# 7seg247b.net
KiCad netlist of a schematic drawn in EAGLE
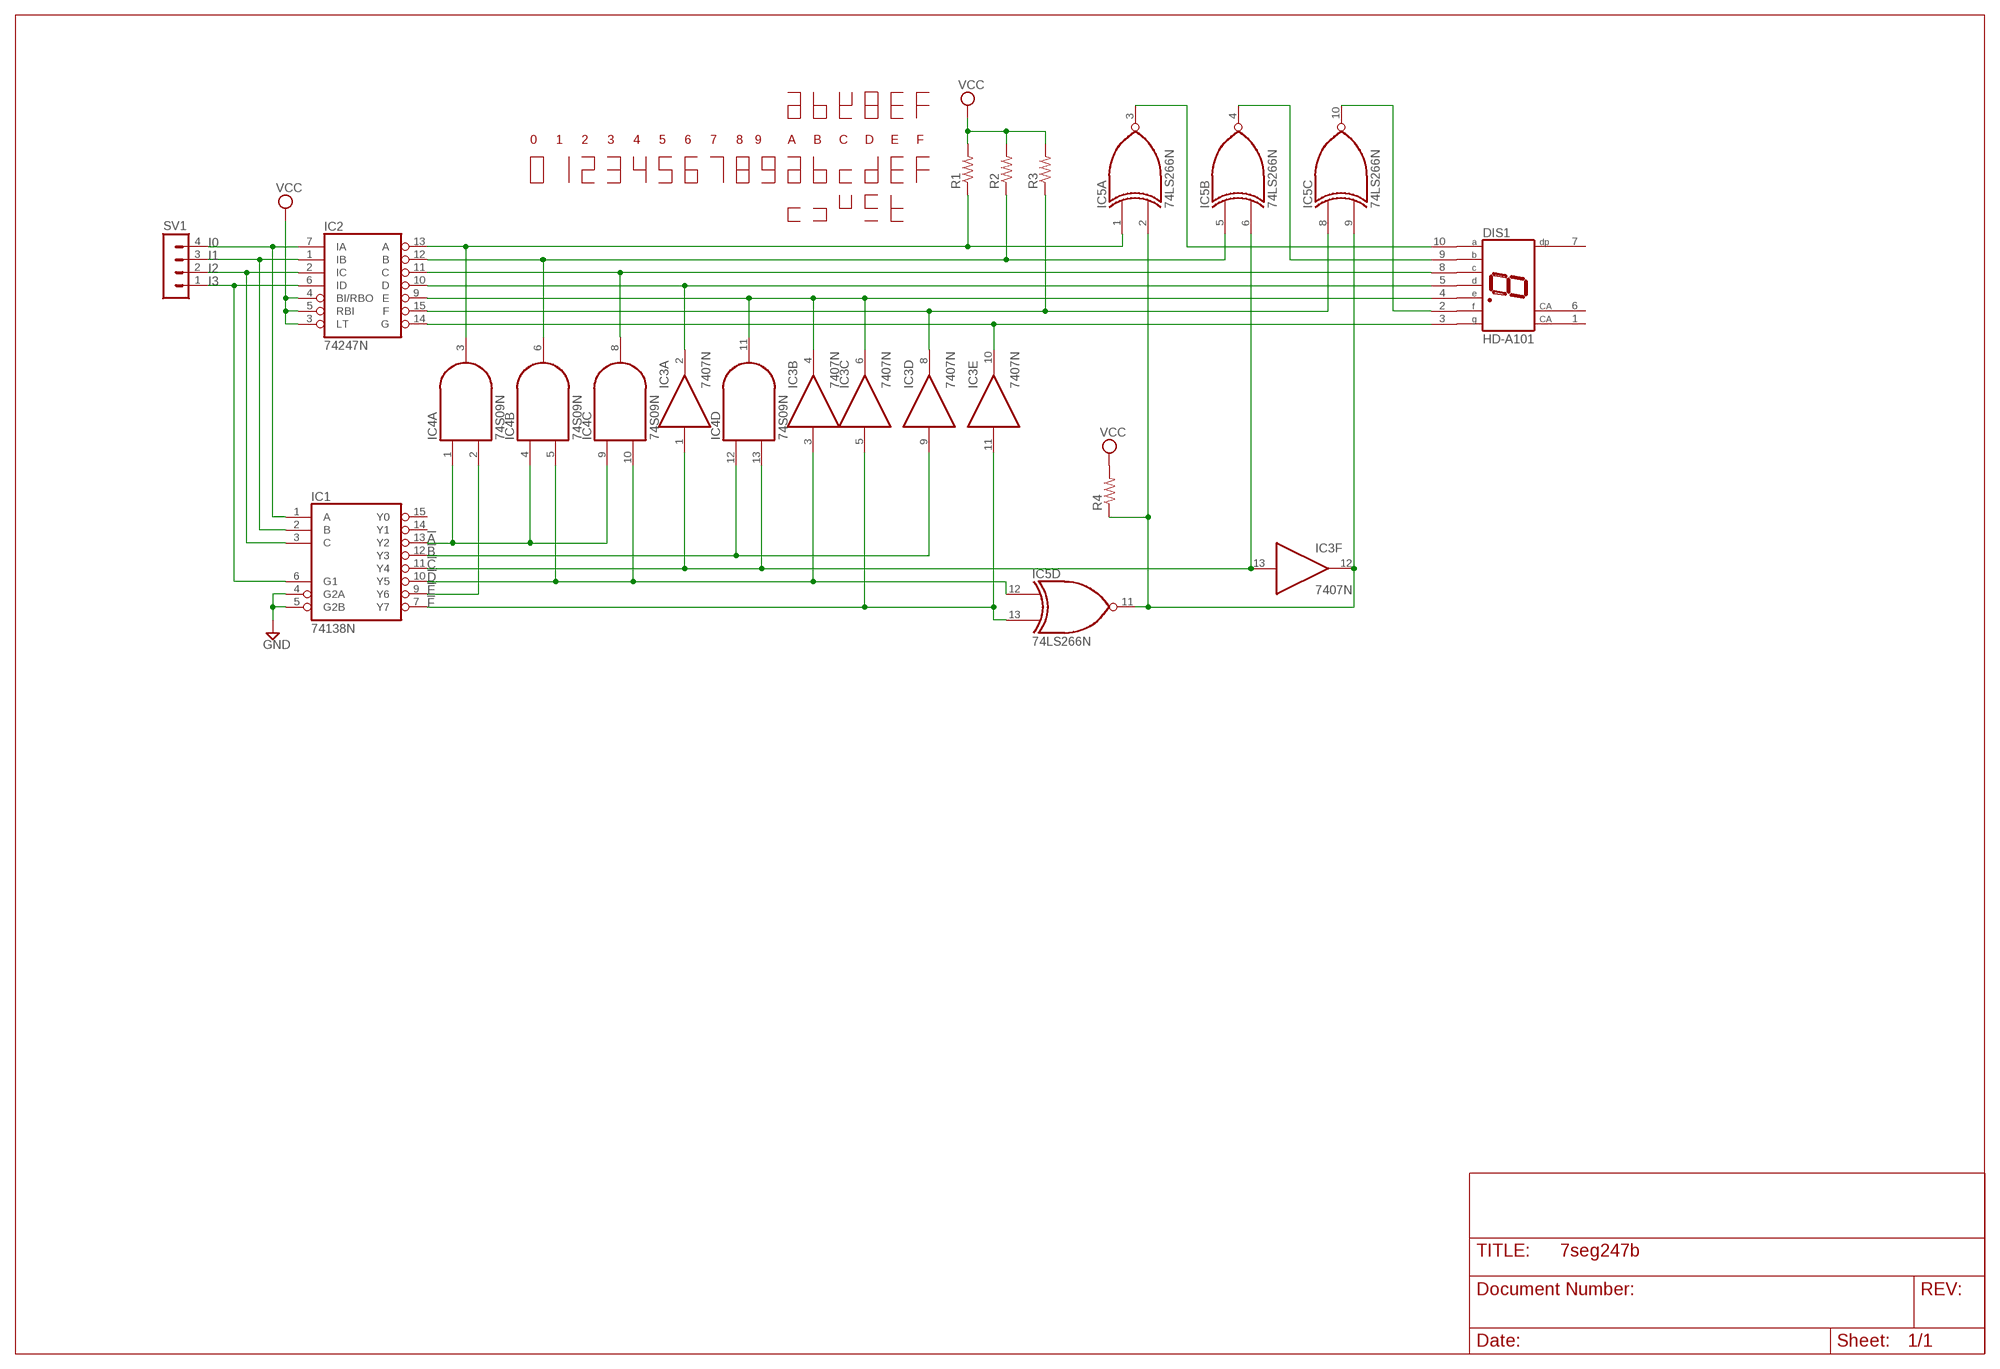
[diagram p0: schematic, sheet 1]

(export (version "E")
  (design (tool "Eeschema 10.0.6"))
  (components
    (comp (ref "DIS1")
      (value "HD-A101")
      (footprint "eagle-import:HDSP-A")
      (libsource (lib "eagle-import") (part "HD-A101"))
    )
    (comp (ref "IC1")
      (value "74138N")
      (footprint "eagle-import:DIL16")
      (libsource (lib "eagle-import") (part "74138NS"))
    )
    (comp (ref "IC2")
      (value "74247N")
      (footprint "eagle-import:DIL16")
      (libsource (lib "eagle-import") (part "7446N"))
    )
    (comp (ref "IC3")
      (value "7407N")
      (footprint "eagle-import:DIL14")
      (libsource (lib "eagle-import") (part "7407N"))
    )
    (comp (ref "IC4")
      (value "74S09N")
      (footprint "eagle-import:DIL14")
      (libsource (lib "eagle-import") (part "7409NS"))
    )
    (comp (ref "IC5")
      (value "74LS266N")
      (footprint "eagle-import:DIL14")
      (libsource (lib "eagle-import") (part "74266NLS"))
    )
    (comp (ref "R1")
      (value "R-US_0207/10")
      (footprint "eagle-import:0207_10")
      (libsource (lib "eagle-import") (part "R-US_0207/10"))
    )
    (comp (ref "R2")
      (value "R-US_0207/10")
      (footprint "eagle-import:0207_10")
      (libsource (lib "eagle-import") (part "R-US_0207/10"))
    )
    (comp (ref "R3")
      (value "R-US_0207/10")
      (footprint "eagle-import:0207_10")
      (libsource (lib "eagle-import") (part "R-US_0207/10"))
    )
    (comp (ref "R4")
      (value "R-US_0207/10")
      (footprint "eagle-import:0207_10")
      (libsource (lib "eagle-import") (part "R-US_0207/10"))
    )
    (comp (ref "SV1")
      (value "MA04-1")
      (footprint "eagle-import:MA04-1")
      (libsource (lib "eagle-import") (part "MA04-1"))
    )
  )
  (nets
    (net (code "1") (name "/I0") (class "Default")
      (node (ref "IC1") (pin "1") (pinfunction "A_1") (pintype "input"))
      (node (ref "IC2") (pin "7") (pinfunction "IA_7") (pintype "input"))
      (node (ref "SV1") (pin "4") (pinfunction "4_4") (pintype "passive"))
    )
    (net (code "2") (name "/I1") (class "Default")
      (node (ref "IC1") (pin "2") (pinfunction "B_2") (pintype "input"))
      (node (ref "IC2") (pin "1") (pinfunction "IB_1") (pintype "input"))
      (node (ref "SV1") (pin "3") (pinfunction "3_3") (pintype "passive"))
    )
    (net (code "3") (name "/I2") (class "Default")
      (node (ref "IC1") (pin "3") (pinfunction "C_3") (pintype "input"))
      (node (ref "IC2") (pin "2") (pinfunction "IC_2") (pintype "input"))
      (node (ref "SV1") (pin "2") (pinfunction "2_2") (pintype "passive"))
    )
    (net (code "4") (name "/I3") (class "Default")
      (node (ref "IC1") (pin "6") (pinfunction "G1_6") (pintype "input"))
      (node (ref "IC2") (pin "6") (pinfunction "ID_6") (pintype "input"))
      (node (ref "SV1") (pin "1") (pinfunction "1_1") (pintype "passive"))
    )
    (net (code "5") (name "/~{A}") (class "Default")
      (node (ref "IC1") (pin "13") (pinfunction "Y2_13") (pintype "output"))
      (node (ref "IC4") (pin "1") (pinfunction "I0_1") (pintype "input"))
      (node (ref "IC4") (pin "4") (pinfunction "I0_4") (pintype "input"))
      (node (ref "IC4") (pin "9") (pinfunction "I0_9") (pintype "input"))
    )
    (net (code "6") (name "/~{B}") (class "Default")
      (node (ref "IC1") (pin "12") (pinfunction "Y3_12") (pintype "output"))
      (node (ref "IC3") (pin "9") (pinfunction "I_9") (pintype "input"))
      (node (ref "IC4") (pin "12") (pinfunction "I0_12") (pintype "input"))
    )
    (net (code "7") (name "/~{C}") (class "Default")
      (node (ref "IC1") (pin "11") (pinfunction "Y4_11") (pintype "output"))
      (node (ref "IC3") (pin "1") (pinfunction "I_1") (pintype "input"))
      (node (ref "IC3") (pin "13") (pinfunction "I_13") (pintype "input"))
      (node (ref "IC4") (pin "13") (pinfunction "I1_13") (pintype "input"))
      (node (ref "IC5") (pin "6") (pinfunction "I1_6") (pintype "input"))
    )
    (net (code "8") (name "/~{D}") (class "Default")
      (node (ref "IC1") (pin "10") (pinfunction "Y5_10") (pintype "output"))
      (node (ref "IC3") (pin "3") (pinfunction "I_3") (pintype "input"))
      (node (ref "IC4") (pin "10") (pinfunction "I1_10") (pintype "input"))
      (node (ref "IC4") (pin "5") (pinfunction "I1_5") (pintype "input"))
      (node (ref "IC5") (pin "12") (pinfunction "I0_12") (pintype "input"))
    )
    (net (code "9") (name "/~{E}") (class "Default")
      (node (ref "IC1") (pin "9") (pinfunction "Y6_9") (pintype "output"))
      (node (ref "IC4") (pin "2") (pinfunction "I1_2") (pintype "input"))
    )
    (net (code "10") (name "/~{F}") (class "Default")
      (node (ref "IC1") (pin "7") (pinfunction "Y7_7") (pintype "output"))
      (node (ref "IC3") (pin "11") (pinfunction "I_11") (pintype "input"))
      (node (ref "IC3") (pin "5") (pinfunction "I_5") (pintype "input"))
      (node (ref "IC5") (pin "13") (pinfunction "I1_13") (pintype "input"))
    )
    (net (code "11") (name "GND") (class "Default")
      (node (ref "IC1") (pin "4") (pinfunction "G2A_4") (pintype "input"))
      (node (ref "IC1") (pin "5") (pinfunction "G2B_5") (pintype "input"))
    )
    (net (code "12") (name "Net-(DIS1-A)") (class "Default")
      (node (ref "DIS1") (pin "10") (pinfunction "A_10") (pintype "passive"))
      (node (ref "IC5") (pin "3") (pinfunction "O_3") (pintype "open_collector"))
    )
    (net (code "13") (name "Net-(DIS1-B)") (class "Default")
      (node (ref "DIS1") (pin "9") (pinfunction "B_9") (pintype "passive"))
      (node (ref "IC5") (pin "4") (pinfunction "O_4") (pintype "open_collector"))
    )
    (net (code "14") (name "Net-(DIS1-C)") (class "Default")
      (node (ref "DIS1") (pin "8") (pinfunction "C_8") (pintype "passive"))
      (node (ref "IC2") (pin "11") (pinfunction "C_11") (pintype "open_collector"))
      (node (ref "IC4") (pin "8") (pinfunction "O_8") (pintype "open_collector"))
    )
    (net (code "15") (name "Net-(DIS1-D)") (class "Default")
      (node (ref "DIS1") (pin "5") (pinfunction "D_5") (pintype "passive"))
      (node (ref "IC2") (pin "10") (pinfunction "D_10") (pintype "open_collector"))
      (node (ref "IC3") (pin "2") (pinfunction "O_2") (pintype "open_collector"))
    )
    (net (code "16") (name "Net-(DIS1-E)") (class "Default")
      (node (ref "DIS1") (pin "4") (pinfunction "E_4") (pintype "passive"))
      (node (ref "IC2") (pin "9") (pinfunction "E_9") (pintype "open_collector"))
      (node (ref "IC3") (pin "4") (pinfunction "O_4") (pintype "open_collector"))
      (node (ref "IC3") (pin "6") (pinfunction "O_6") (pintype "open_collector"))
      (node (ref "IC4") (pin "11") (pinfunction "O_11") (pintype "open_collector"))
    )
    (net (code "17") (name "Net-(DIS1-F)") (class "Default")
      (node (ref "DIS1") (pin "2") (pinfunction "F_2") (pintype "passive"))
      (node (ref "IC5") (pin "10") (pinfunction "O_10") (pintype "open_collector"))
    )
    (net (code "18") (name "Net-(DIS1-G)") (class "Default")
      (node (ref "DIS1") (pin "3") (pinfunction "G_3") (pintype "passive"))
      (node (ref "IC2") (pin "14") (pinfunction "G_14") (pintype "open_collector"))
      (node (ref "IC3") (pin "10") (pinfunction "O_10") (pintype "open_collector"))
    )
    (net (code "19") (name "Net-(IC2A-A)") (class "Default")
      (node (ref "IC2") (pin "13") (pinfunction "A_13") (pintype "open_collector"))
      (node (ref "IC4") (pin "3") (pinfunction "O_3") (pintype "open_collector"))
      (node (ref "IC5") (pin "1") (pinfunction "I0_1") (pintype "input"))
      (node (ref "R1") (pin "1") (pinfunction "1_1") (pintype "passive"))
    )
    (net (code "20") (name "Net-(IC2A-B)") (class "Default")
      (node (ref "IC2") (pin "12") (pinfunction "B_12") (pintype "open_collector"))
      (node (ref "IC4") (pin "6") (pinfunction "O_6") (pintype "open_collector"))
      (node (ref "IC5") (pin "5") (pinfunction "I0_5") (pintype "input"))
      (node (ref "R2") (pin "1") (pinfunction "1_1") (pintype "passive"))
    )
    (net (code "21") (name "Net-(IC2A-F)") (class "Default")
      (node (ref "IC2") (pin "15") (pinfunction "F_15") (pintype "open_collector"))
      (node (ref "IC3") (pin "8") (pinfunction "O_8") (pintype "open_collector"))
      (node (ref "IC5") (pin "8") (pinfunction "I0_8") (pintype "input"))
      (node (ref "R3") (pin "1") (pinfunction "1_1") (pintype "passive"))
    )
    (net (code "22") (name "Net-(IC3F-O)") (class "Default")
      (node (ref "IC3") (pin "12") (pinfunction "O_12") (pintype "open_collector"))
      (node (ref "IC5") (pin "11") (pinfunction "O_11") (pintype "open_collector"))
      (node (ref "IC5") (pin "2") (pinfunction "I1_2") (pintype "input"))
      (node (ref "IC5") (pin "9") (pinfunction "I1_9") (pintype "input"))
      (node (ref "R4") (pin "1") (pinfunction "1_1") (pintype "passive"))
    )
    (net (code "23") (name "VCC") (class "Default")
      (node (ref "IC2") (pin "3") (pinfunction "LT_3") (pintype "input"))
      (node (ref "IC2") (pin "4") (pinfunction "BI/RBO_4") (pintype "input"))
      (node (ref "IC2") (pin "5") (pinfunction "RBI_5") (pintype "input"))
      (node (ref "R1") (pin "2") (pinfunction "2_2") (pintype "passive"))
      (node (ref "R2") (pin "2") (pinfunction "2_2") (pintype "passive"))
      (node (ref "R3") (pin "2") (pinfunction "2_2") (pintype "passive"))
      (node (ref "R4") (pin "2") (pinfunction "2_2") (pintype "passive"))
    )
    (net (code "24") (name "unconnected-(DIS1-CA-Pad1)") (class "Default")
      (node (ref "DIS1") (pin "1") (pinfunction "CA_1") (pintype "passive"))
    )
    (net (code "25") (name "unconnected-(DIS1-CA-Pad6)") (class "Default")
      (node (ref "DIS1") (pin "6") (pinfunction "CA_6") (pintype "passive"))
    )
    (net (code "26") (name "unconnected-(DIS1-DP-Pad7)") (class "Default")
      (node (ref "DIS1") (pin "7") (pinfunction "DP_7") (pintype "passive"))
    )
    (net (code "27") (name "unconnected-(IC1A-Y0-Pad15)") (class "Default")
      (node (ref "IC1") (pin "15") (pinfunction "Y0_15") (pintype "output"))
    )
    (net (code "28") (name "unconnected-(IC1A-Y1-Pad14)") (class "Default")
      (node (ref "IC1") (pin "14") (pinfunction "Y1_14") (pintype "output"))
    )
  )
)
